# clusterPlusOpamp.net
KiCad netlist of a schematic drawn in Altium Designer
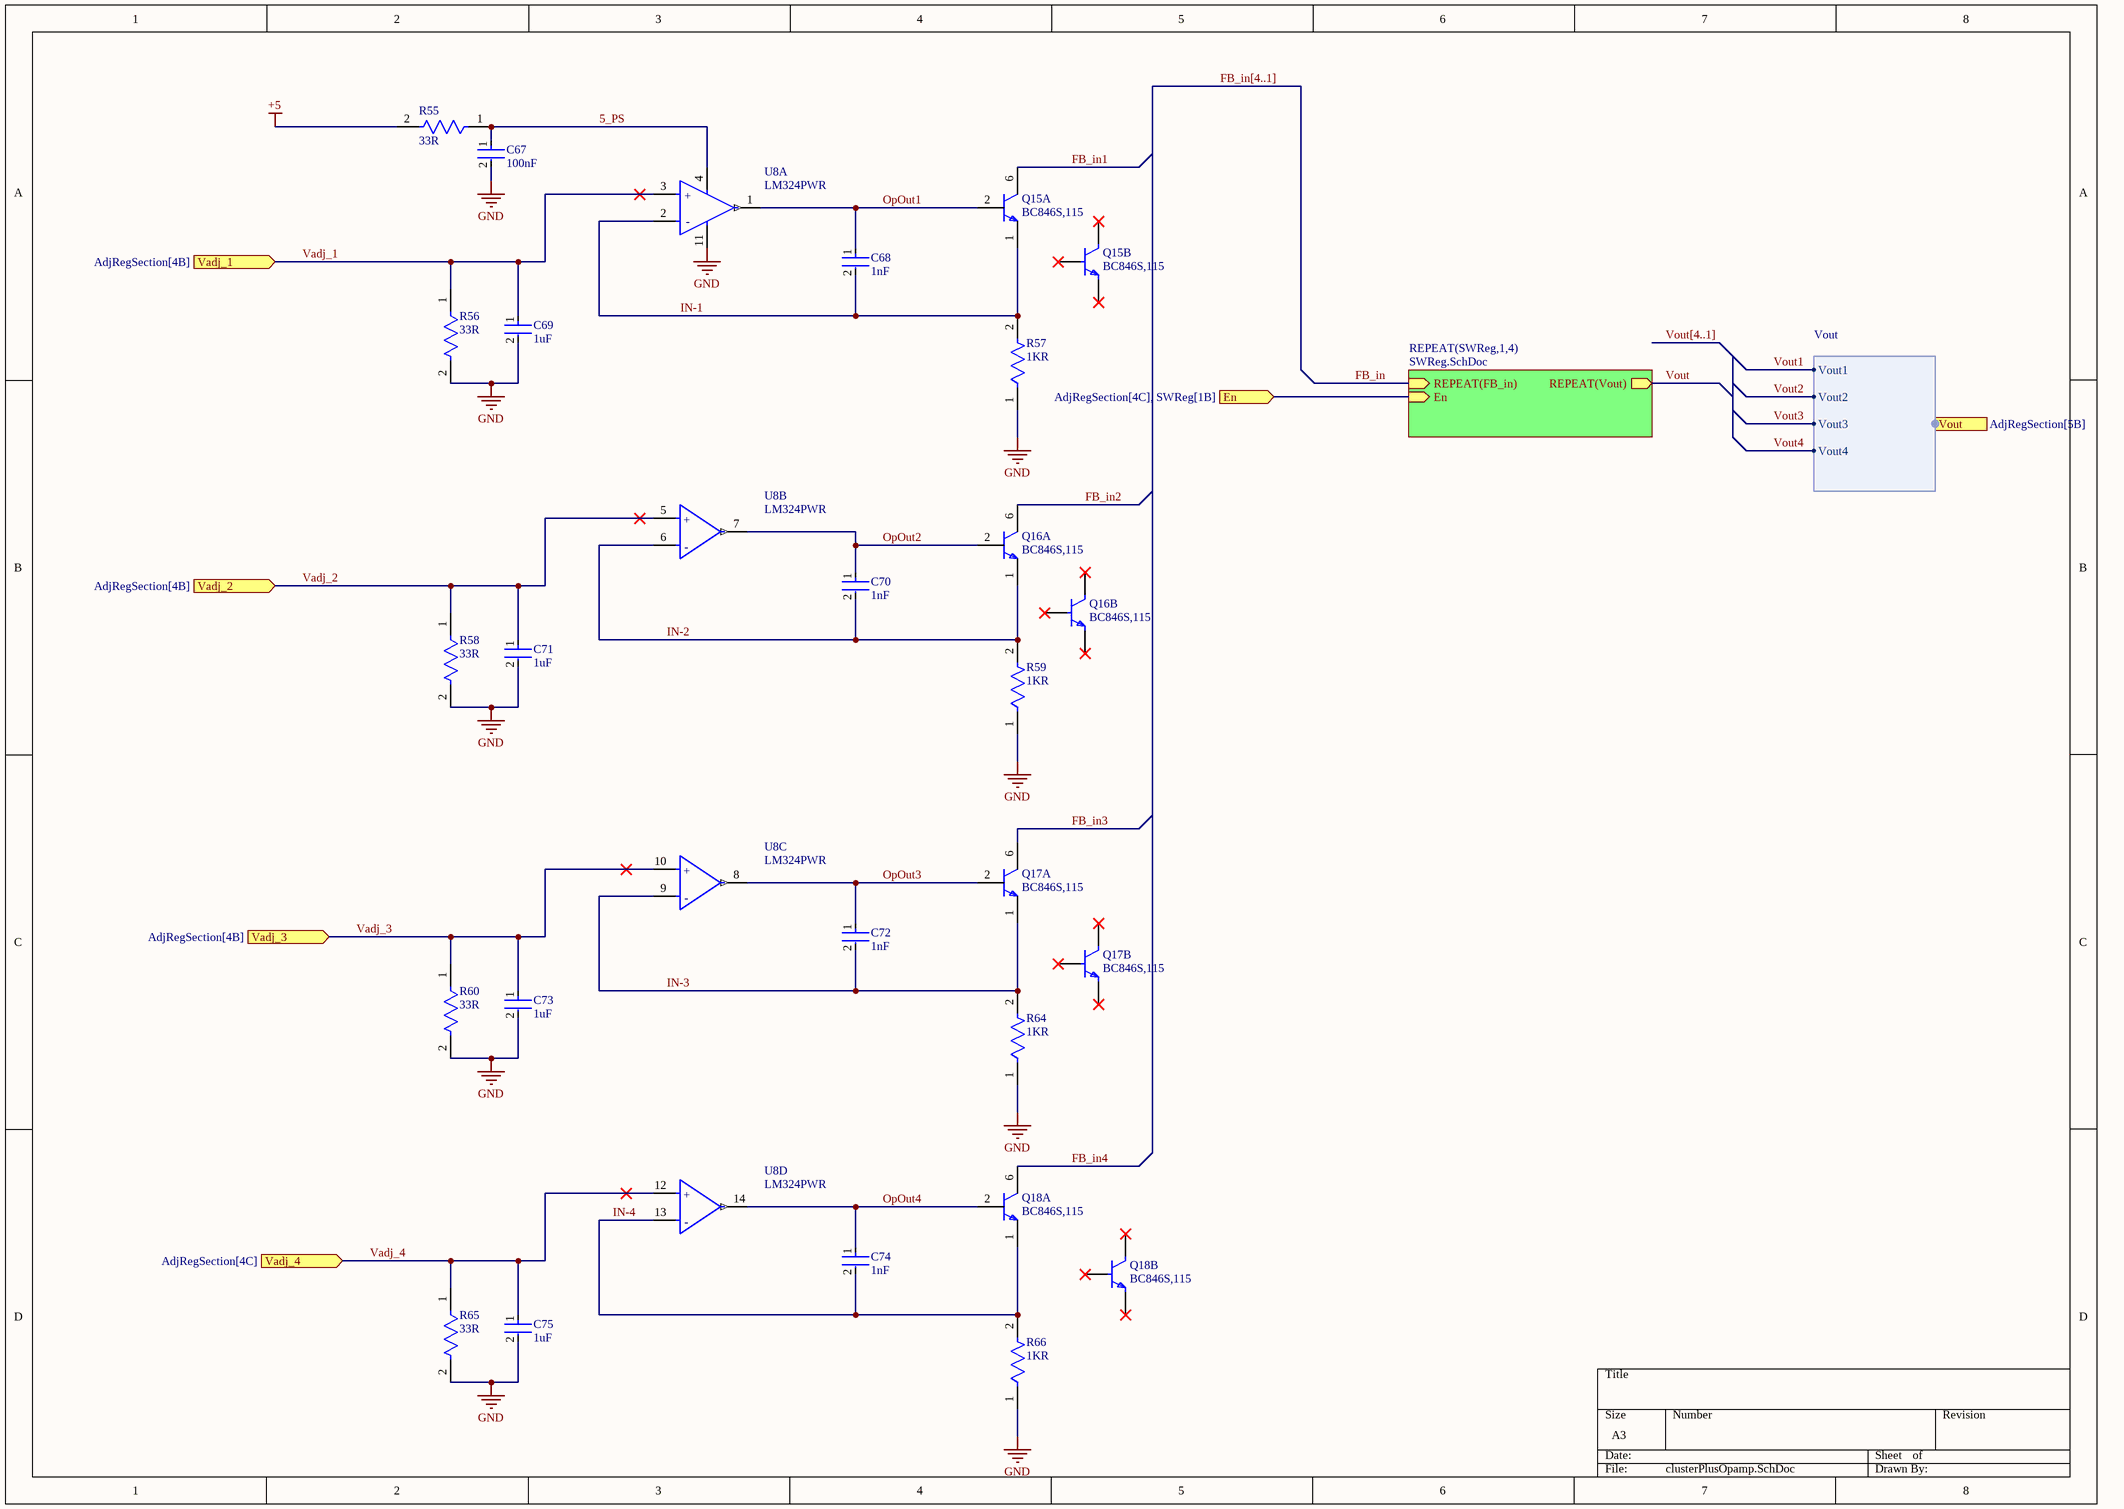
[diagram p0: clusterPlusOpamp.SchDoc]

(export (version "E")
  (design (tool "Eeschema 10.0.6"))
  (components
    (comp (ref "C67")
      (value "100nF")
      (footprint "FP-CC1206-1_25-MFG")
      (description "CAP CER 0.1UF 50V X7R 1206")
      (fields
        (field (name "OCTOPART") "https://octopart.com/cc1206krx7r9bb104-yageo-39467816")
        (field (name "TOLERANCE") "0.1")
      )
      (libsource (lib "Altium Content Vault") (part "11868f565c42a9108669ba33697ecf6"))
    )
    (comp (ref "C68")
      (value "1nF")
      (footprint "FP-CC1206-1_25-MFG")
      (description "CAP CER 0.1UF 50V X7R 1206")
      (fields
        (field (name "OCTOPART") "https://octopart.com/cc1206krx7r9bb104-yageo-39467816")
        (field (name "TOLERANCE") "0.1")
      )
      (libsource (lib "Altium Content Vault") (part "11868f565c42a9108669ba33697ecf6"))
    )
    (comp (ref "C69")
      (value "1uF")
      (footprint "FP-CC1206-1_25-MFG")
      (description "CAP CER 0.1UF 50V X7R 1206")
      (fields
        (field (name "OCTOPART") "https://octopart.com/cc1206krx7r9bb104-yageo-39467816")
        (field (name "TOLERANCE") "0.1")
      )
      (libsource (lib "Altium Content Vault") (part "11868f565c42a9108669ba33697ecf6"))
    )
    (comp (ref "C70")
      (value "1nF")
      (footprint "FP-CC1206-1_25-MFG")
      (description "CAP CER 0.1UF 50V X7R 1206")
      (fields
        (field (name "OCTOPART") "https://octopart.com/cc1206krx7r9bb104-yageo-39467816")
        (field (name "TOLERANCE") "0.1")
      )
      (libsource (lib "Altium Content Vault") (part "11868f565c42a9108669ba33697ecf6"))
    )
    (comp (ref "C71")
      (value "1uF")
      (footprint "FP-CC1206-1_25-MFG")
      (description "CAP CER 0.1UF 50V X7R 1206")
      (fields
        (field (name "OCTOPART") "https://octopart.com/cc1206krx7r9bb104-yageo-39467816")
        (field (name "TOLERANCE") "0.1")
      )
      (libsource (lib "Altium Content Vault") (part "11868f565c42a9108669ba33697ecf6"))
    )
    (comp (ref "C72")
      (value "1nF")
      (footprint "FP-CC1206-1_25-MFG")
      (description "CAP CER 0.1UF 50V X7R 1206")
      (fields
        (field (name "OCTOPART") "https://octopart.com/cc1206krx7r9bb104-yageo-39467816")
        (field (name "TOLERANCE") "0.1")
      )
      (libsource (lib "Altium Content Vault") (part "11868f565c42a9108669ba33697ecf6"))
    )
    (comp (ref "C73")
      (value "1uF")
      (footprint "FP-CC1206-1_25-MFG")
      (description "CAP CER 0.1UF 50V X7R 1206")
      (fields
        (field (name "OCTOPART") "https://octopart.com/cc1206krx7r9bb104-yageo-39467816")
        (field (name "TOLERANCE") "0.1")
      )
      (libsource (lib "Altium Content Vault") (part "11868f565c42a9108669ba33697ecf6"))
    )
    (comp (ref "C74")
      (value "1nF")
      (footprint "FP-CC1206-1_25-MFG")
      (description "CAP CER 0.1UF 50V X7R 1206")
      (fields
        (field (name "OCTOPART") "https://octopart.com/cc1206krx7r9bb104-yageo-39467816")
        (field (name "TOLERANCE") "0.1")
      )
      (libsource (lib "Altium Content Vault") (part "11868f565c42a9108669ba33697ecf6"))
    )
    (comp (ref "C75")
      (value "1uF")
      (footprint "FP-CC1206-1_25-MFG")
      (description "CAP CER 0.1UF 50V X7R 1206")
      (fields
        (field (name "OCTOPART") "https://octopart.com/cc1206krx7r9bb104-yageo-39467816")
        (field (name "TOLERANCE") "0.1")
      )
      (libsource (lib "Altium Content Vault") (part "11868f565c42a9108669ba33697ecf6"))
    )
    (comp (ref "Q15")
      (value "BC846S,115")
      (footprint "FP-SOT363-MFG")
      (description "TRANS 2NPN 65V 0.1A 6TSSOP")
      (fields
        (field (name "MANUFACTURER") "Nexperia")
        (field (name "OCTOPART") "https://octopart.com/bc846s%2C115-nexperia-78739099")
      )
      (libsource (lib "Altium Content Vault") (part "d6cee8eb750607eedcaf46266e24fa2"))
    )
    (comp (ref "Q16")
      (value "BC846S,115")
      (footprint "FP-SOT363-MFG")
      (description "TRANS 2NPN 65V 0.1A 6TSSOP")
      (fields
        (field (name "MANUFACTURER") "Nexperia")
        (field (name "OCTOPART") "https://octopart.com/bc846s%2C115-nexperia-78739099")
      )
      (libsource (lib "Altium Content Vault") (part "d6cee8eb750607eedcaf46266e24fa2"))
    )
    (comp (ref "Q17")
      (value "BC846S,115")
      (footprint "FP-SOT363-MFG")
      (description "TRANS 2NPN 65V 0.1A 6TSSOP")
      (fields
        (field (name "MANUFACTURER") "Nexperia")
        (field (name "OCTOPART") "https://octopart.com/bc846s%2C115-nexperia-78739099")
      )
      (libsource (lib "Altium Content Vault") (part "d6cee8eb750607eedcaf46266e24fa2"))
    )
    (comp (ref "Q18")
      (value "BC846S,115")
      (footprint "FP-SOT363-MFG")
      (description "TRANS 2NPN 65V 0.1A 6TSSOP")
      (fields
        (field (name "MANUFACTURER") "Nexperia")
        (field (name "OCTOPART") "https://octopart.com/bc846s%2C115-nexperia-78739099")
      )
      (libsource (lib "Altium Content Vault") (part "d6cee8eb750607eedcaf46266e24fa2"))
    )
    (comp (ref "R55")
      (value "33R")
      (footprint "FP-RC0603-0_55-MFG")
      (description "RES SMD 100K OHM 1% 1/10W 0603")
      (fields (field (name "TOLERANCE") "1%"))
      (libsource (lib "Altium Content Vault") (part "1029c3af85768c4190bb7ad29bc67b5"))
    )
    (comp (ref "R56")
      (value "33R")
      (footprint "FP-RC0603-0_55-MFG")
      (description "RES SMD 100K OHM 1% 1/10W 0603")
      (fields (field (name "TOLERANCE") "1%"))
      (libsource (lib "Altium Content Vault") (part "1029c3af85768c4190bb7ad29bc67b5"))
    )
    (comp (ref "R57")
      (value "1KR")
      (footprint "FP-RC0603-0_55-MFG")
      (description "RES SMD 100K OHM 1% 1/10W 0603")
      (fields (field (name "TOLERANCE") "1%"))
      (libsource (lib "Altium Content Vault") (part "1029c3af85768c4190bb7ad29bc67b5"))
    )
    (comp (ref "R58")
      (value "33R")
      (footprint "FP-RC0603-0_55-MFG")
      (description "RES SMD 100K OHM 1% 1/10W 0603")
      (fields (field (name "TOLERANCE") "1%"))
      (libsource (lib "Altium Content Vault") (part "1029c3af85768c4190bb7ad29bc67b5"))
    )
    (comp (ref "R59")
      (value "1KR")
      (footprint "FP-RC0603-0_55-MFG")
      (description "RES SMD 100K OHM 1% 1/10W 0603")
      (fields (field (name "TOLERANCE") "1%"))
      (libsource (lib "Altium Content Vault") (part "1029c3af85768c4190bb7ad29bc67b5"))
    )
    (comp (ref "R60")
      (value "33R")
      (footprint "FP-RC0603-0_55-MFG")
      (description "RES SMD 100K OHM 1% 1/10W 0603")
      (fields (field (name "TOLERANCE") "1%"))
      (libsource (lib "Altium Content Vault") (part "1029c3af85768c4190bb7ad29bc67b5"))
    )
    (comp (ref "R64")
      (value "1KR")
      (footprint "FP-RC0603-0_55-MFG")
      (description "RES SMD 100K OHM 1% 1/10W 0603")
      (fields (field (name "TOLERANCE") "1%"))
      (libsource (lib "Altium Content Vault") (part "1029c3af85768c4190bb7ad29bc67b5"))
    )
    (comp (ref "R65")
      (value "33R")
      (footprint "FP-RC0603-0_55-MFG")
      (description "RES SMD 100K OHM 1% 1/10W 0603")
      (fields (field (name "TOLERANCE") "1%"))
      (libsource (lib "Altium Content Vault") (part "1029c3af85768c4190bb7ad29bc67b5"))
    )
    (comp (ref "R66")
      (value "1KR")
      (footprint "FP-RC0603-0_55-MFG")
      (description "RES SMD 100K OHM 1% 1/10W 0603")
      (fields (field (name "TOLERANCE") "1%"))
      (libsource (lib "Altium Content Vault") (part "1029c3af85768c4190bb7ad29bc67b5"))
    )
    (comp (ref "U8")
      (value "LM324PWR")
      (footprint "FP-PW0014A-MFG")
      (description "IC OPAMP GP 4 CIRCUIT 14TSSOP")
      (fields
        (field (name "OCTOPART") "https://octopart.com/lm324pwr-texas+instruments-410375")
        (field (name "MANUFACTURER") "Texas Instruments")
      )
      (libsource (lib "Altium Content Vault") (part "b02d0cb41c0d90ddc6f34c0e90b5c12"))
    )
  )
  (nets
    (net (code "1") (name "+5") (class "Default")
      (node (ref "R55") (pin "2") (pinfunction "2_2") (pintype "passive"))
    )
    (net (code "2") (name "/5_PS") (class "Default")
      (node (ref "C67") (pin "1") (pinfunction "1_1") (pintype "passive"))
      (node (ref "R55") (pin "1") (pinfunction "1_1") (pintype "passive"))
      (node (ref "U8") (pin "4") (pinfunction "VCC_4") (pintype "power_in"))
    )
    (net (code "5") (name "/FB_in1") (class "Default")
      (node (ref "Q15") (pin "6") (pinfunction "C_6") (pintype "passive"))
    )
    (net (code "6") (name "/FB_in2") (class "Default")
      (node (ref "Q16") (pin "6") (pinfunction "C_6") (pintype "passive"))
    )
    (net (code "7") (name "/FB_in3") (class "Default")
      (node (ref "Q17") (pin "6") (pinfunction "C_6") (pintype "passive"))
    )
    (net (code "8") (name "/FB_in4") (class "Default")
      (node (ref "Q18") (pin "6") (pinfunction "C_6") (pintype "passive"))
    )
    (net (code "10") (name "/IN-1") (class "Default")
      (node (ref "C68") (pin "2") (pinfunction "2_2") (pintype "passive"))
      (node (ref "Q15") (pin "1") (pinfunction "E_1") (pintype "passive"))
      (node (ref "R57") (pin "2") (pinfunction "2_2") (pintype "passive"))
      (node (ref "U8") (pin "2") (pinfunction "1IN-_2") (pintype "tri_state"))
    )
    (net (code "11") (name "/IN-2") (class "Default")
      (node (ref "C70") (pin "2") (pinfunction "2_2") (pintype "passive"))
      (node (ref "Q16") (pin "1") (pinfunction "E_1") (pintype "passive"))
      (node (ref "R59") (pin "2") (pinfunction "2_2") (pintype "passive"))
      (node (ref "U8") (pin "6") (pinfunction "2IN-_6") (pintype "tri_state"))
    )
    (net (code "12") (name "/IN-3") (class "Default")
      (node (ref "C72") (pin "2") (pinfunction "2_2") (pintype "passive"))
      (node (ref "Q17") (pin "1") (pinfunction "E_1") (pintype "passive"))
      (node (ref "R64") (pin "2") (pinfunction "2_2") (pintype "passive"))
      (node (ref "U8") (pin "9") (pinfunction "3IN-_9") (pintype "tri_state"))
    )
    (net (code "13") (name "/IN-4") (class "Default")
      (node (ref "C74") (pin "2") (pinfunction "2_2") (pintype "passive"))
      (node (ref "Q18") (pin "1") (pinfunction "E_1") (pintype "passive"))
      (node (ref "R66") (pin "2") (pinfunction "2_2") (pintype "passive"))
      (node (ref "U8") (pin "13") (pinfunction "4IN-_13") (pintype "tri_state"))
    )
    (net (code "14") (name "/OpOut1") (class "Default")
      (node (ref "C68") (pin "1") (pinfunction "1_1") (pintype "passive"))
      (node (ref "Q15") (pin "2") (pinfunction "B_2") (pintype "passive"))
      (node (ref "U8") (pin "1") (pinfunction "1OUT_1") (pintype "output"))
    )
    (net (code "15") (name "/OpOut2") (class "Default")
      (node (ref "C70") (pin "1") (pinfunction "1_1") (pintype "passive"))
      (node (ref "Q16") (pin "2") (pinfunction "B_2") (pintype "passive"))
      (node (ref "U8") (pin "7") (pinfunction "2OUT_7") (pintype "output"))
    )
    (net (code "16") (name "/OpOut3") (class "Default")
      (node (ref "C72") (pin "1") (pinfunction "1_1") (pintype "passive"))
      (node (ref "Q17") (pin "2") (pinfunction "B_2") (pintype "passive"))
      (node (ref "U8") (pin "8") (pinfunction "3OUT_8") (pintype "output"))
    )
    (net (code "17") (name "/OpOut4") (class "Default")
      (node (ref "C74") (pin "1") (pinfunction "1_1") (pintype "passive"))
      (node (ref "Q18") (pin "2") (pinfunction "B_2") (pintype "passive"))
      (node (ref "U8") (pin "14") (pinfunction "4OUT_14") (pintype "output"))
    )
    (net (code "18") (name "/Vadj_1") (class "Default")
      (node (ref "C69") (pin "1") (pinfunction "1_1") (pintype "passive"))
      (node (ref "R56") (pin "1") (pinfunction "1_1") (pintype "passive"))
      (node (ref "U8") (pin "3") (pinfunction "1IN+_3") (pintype "tri_state"))
    )
    (net (code "19") (name "/Vadj_2") (class "Default")
      (node (ref "C71") (pin "1") (pinfunction "1_1") (pintype "passive"))
      (node (ref "R58") (pin "1") (pinfunction "1_1") (pintype "passive"))
      (node (ref "U8") (pin "5") (pinfunction "2IN+_5") (pintype "tri_state"))
    )
    (net (code "20") (name "/Vadj_3") (class "Default")
      (node (ref "C73") (pin "1") (pinfunction "1_1") (pintype "passive"))
      (node (ref "R60") (pin "1") (pinfunction "1_1") (pintype "passive"))
      (node (ref "U8") (pin "10") (pinfunction "3IN+_10") (pintype "tri_state"))
    )
    (net (code "21") (name "/Vadj_4") (class "Default")
      (node (ref "C75") (pin "1") (pinfunction "1_1") (pintype "passive"))
      (node (ref "R65") (pin "1") (pinfunction "1_1") (pintype "passive"))
      (node (ref "U8") (pin "12") (pinfunction "4IN+_12") (pintype "tri_state"))
    )
    (net (code "29") (name "GND") (class "Default")
      (node (ref "C67") (pin "2") (pinfunction "2_2") (pintype "passive"))
      (node (ref "C69") (pin "2") (pinfunction "2_2") (pintype "passive"))
      (node (ref "C71") (pin "2") (pinfunction "2_2") (pintype "passive"))
      (node (ref "C73") (pin "2") (pinfunction "2_2") (pintype "passive"))
      (node (ref "C75") (pin "2") (pinfunction "2_2") (pintype "passive"))
      (node (ref "R56") (pin "2") (pinfunction "2_2") (pintype "passive"))
      (node (ref "R57") (pin "1") (pinfunction "1_1") (pintype "passive"))
      (node (ref "R58") (pin "2") (pinfunction "2_2") (pintype "passive"))
      (node (ref "R59") (pin "1") (pinfunction "1_1") (pintype "passive"))
      (node (ref "R60") (pin "2") (pinfunction "2_2") (pintype "passive"))
      (node (ref "R64") (pin "1") (pinfunction "1_1") (pintype "passive"))
      (node (ref "R65") (pin "2") (pinfunction "2_2") (pintype "passive"))
      (node (ref "R66") (pin "1") (pinfunction "1_1") (pintype "passive"))
      (node (ref "U8") (pin "11") (pinfunction "GND_11") (pintype "power_in"))
    )
    (net (code "30") (name "unconnected-(Q15B-B-Pad5)") (class "Default")
      (node (ref "Q15") (pin "5") (pinfunction "B_5") (pintype "passive+no_connect"))
    )
    (net (code "31") (name "unconnected-(Q15B-C-Pad3)") (class "Default")
      (node (ref "Q15") (pin "3") (pinfunction "C_3") (pintype "passive+no_connect"))
    )
    (net (code "32") (name "unconnected-(Q15B-E-Pad4)") (class "Default")
      (node (ref "Q15") (pin "4") (pinfunction "E_4") (pintype "passive+no_connect"))
    )
    (net (code "33") (name "unconnected-(Q16B-B-Pad5)") (class "Default")
      (node (ref "Q16") (pin "5") (pinfunction "B_5") (pintype "passive+no_connect"))
    )
    (net (code "34") (name "unconnected-(Q16B-C-Pad3)") (class "Default")
      (node (ref "Q16") (pin "3") (pinfunction "C_3") (pintype "passive+no_connect"))
    )
    (net (code "35") (name "unconnected-(Q16B-E-Pad4)") (class "Default")
      (node (ref "Q16") (pin "4") (pinfunction "E_4") (pintype "passive+no_connect"))
    )
    (net (code "36") (name "unconnected-(Q17B-B-Pad5)") (class "Default")
      (node (ref "Q17") (pin "5") (pinfunction "B_5") (pintype "passive+no_connect"))
    )
    (net (code "37") (name "unconnected-(Q17B-C-Pad3)") (class "Default")
      (node (ref "Q17") (pin "3") (pinfunction "C_3") (pintype "passive+no_connect"))
    )
    (net (code "38") (name "unconnected-(Q17B-E-Pad4)") (class "Default")
      (node (ref "Q17") (pin "4") (pinfunction "E_4") (pintype "passive+no_connect"))
    )
    (net (code "39") (name "unconnected-(Q18B-B-Pad5)") (class "Default")
      (node (ref "Q18") (pin "5") (pinfunction "B_5") (pintype "passive+no_connect"))
    )
    (net (code "40") (name "unconnected-(Q18B-C-Pad3)") (class "Default")
      (node (ref "Q18") (pin "3") (pinfunction "C_3") (pintype "passive+no_connect"))
    )
    (net (code "41") (name "unconnected-(Q18B-E-Pad4)") (class "Default")
      (node (ref "Q18") (pin "4") (pinfunction "E_4") (pintype "passive+no_connect"))
    )
  )
)
